# ATMEGA162.net
KiCad netlist of a schematic drawn in Altium Designer
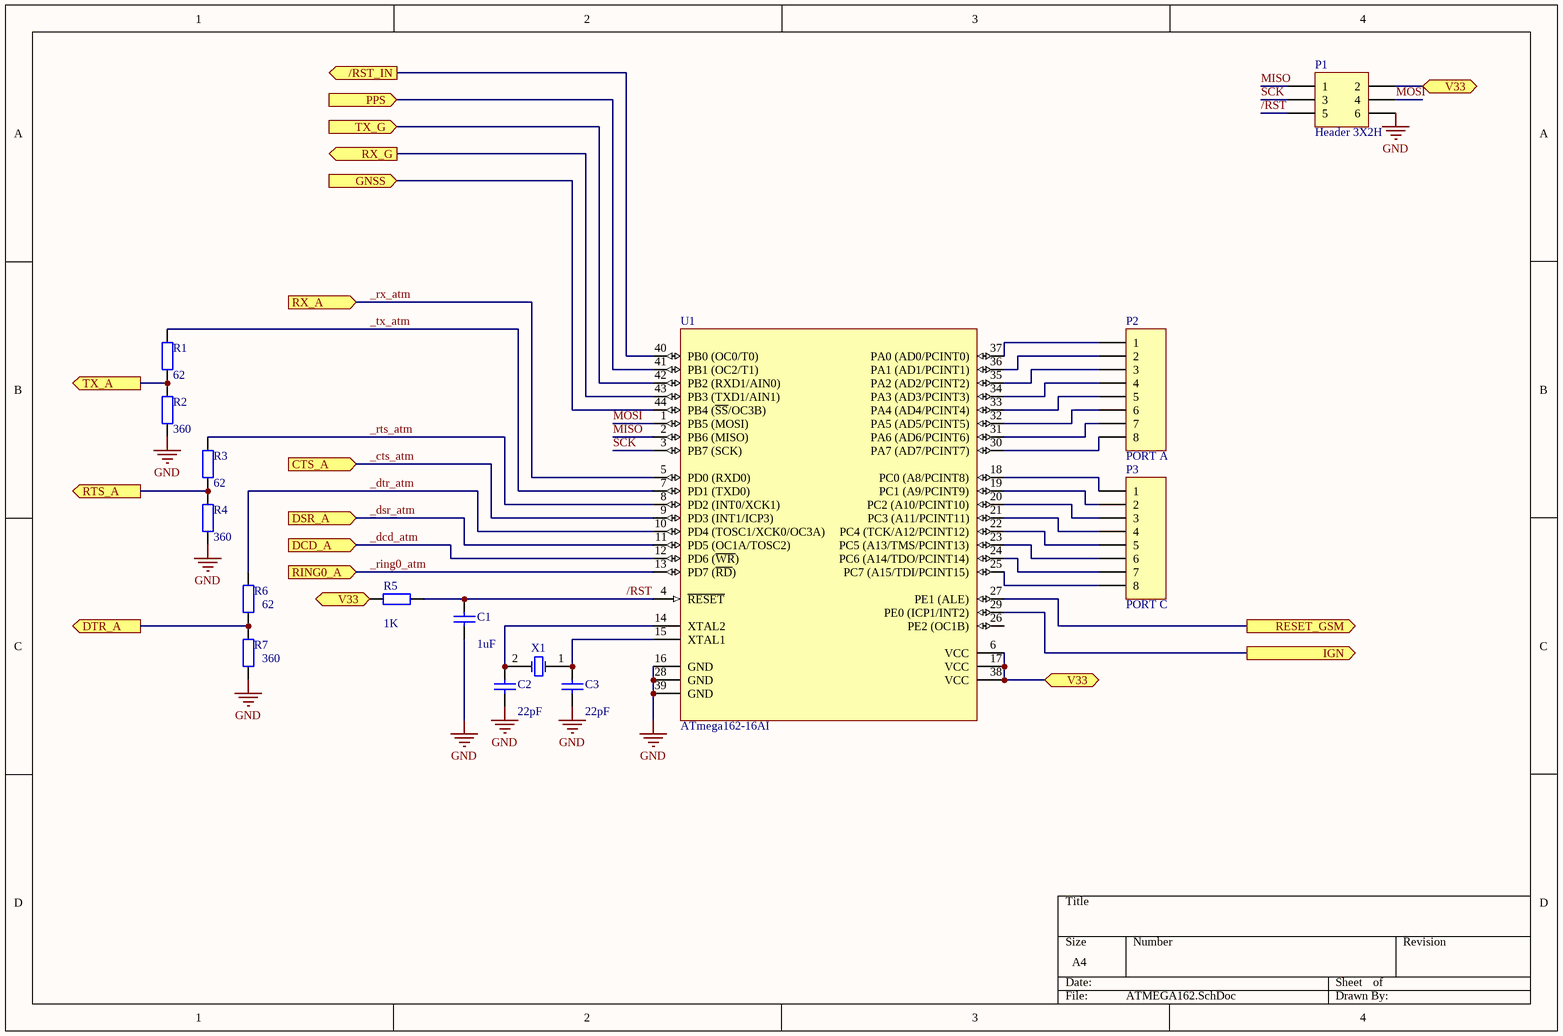
[diagram p0: ATMEGA162.SchDoc]

(export (version "E")
  (design (tool "Eeschema 10.0.6"))
  (components
    (comp (ref "C1")
      (value "1uF")
      (footprint "RAD-0.1")
      (description "Capacitor")
      (fields (field (name "Comment") "Cap") (field (name "PUBLISHER") "Altium Limited"))
      (libsource (lib "Miscellaneous Devices") (part "Cap"))
    )
    (comp (ref "C2")
      (value "22pF")
      (footprint "RAD-0.1")
      (description "Capacitor")
      (fields (field (name "Comment") "Cap") (field (name "PUBLISHER") "Altium Limited"))
      (libsource (lib "Miscellaneous Devices") (part "Cap"))
    )
    (comp (ref "C3")
      (value "22pF")
      (footprint "RAD-0.1")
      (description "Capacitor")
      (fields (field (name "Comment") "Cap") (field (name "PUBLISHER") "Altium Limited"))
      (libsource (lib "Miscellaneous Devices") (part "Cap"))
    )
    (comp (ref "P1")
      (value "Header 3X2H")
      (footprint "HDR2X3H")
      (description "Header, 3-Pin, Dual row, Right Angle")
      (fields (field (name "PUBLISHER") "Altium Limited"))
      (libsource (lib "Miscellaneous Connectors") (part "Header 3X2H"))
    )
    (comp (ref "P2")
      (value "PORT A")
      (footprint "HDR1X8H")
      (description "Header, 8-Pin, Right Angle")
      (fields (field (name "PUBLISHER") "Altium Limited"))
      (libsource (lib "Miscellaneous Connectors") (part "Header 8H"))
    )
    (comp (ref "P3")
      (value "PORT C")
      (footprint "HDR1X8H")
      (description "Header, 8-Pin, Right Angle")
      (fields (field (name "PUBLISHER") "Altium Limited"))
      (libsource (lib "Miscellaneous Connectors") (part "Header 8H"))
    )
    (comp (ref "R1")
      (value "62")
      (footprint "AXIAL-0.4")
      (description "Resistor")
      (fields (field (name "Comment") "Res2") (field (name "PUBLISHER") "Altium Limited"))
      (libsource (lib "Miscellaneous Devices") (part "Res2"))
    )
    (comp (ref "R2")
      (value "360")
      (footprint "AXIAL-0.4")
      (description "Resistor")
      (fields (field (name "Comment") "Res2") (field (name "PUBLISHER") "Altium Limited"))
      (libsource (lib "Miscellaneous Devices") (part "Res2"))
    )
    (comp (ref "R3")
      (value "62")
      (footprint "AXIAL-0.4")
      (description "Resistor")
      (fields (field (name "Comment") "Res2") (field (name "PUBLISHER") "Altium Limited"))
      (libsource (lib "Miscellaneous Devices") (part "Res2"))
    )
    (comp (ref "R4")
      (value "360")
      (footprint "AXIAL-0.4")
      (description "Resistor")
      (fields (field (name "Comment") "Res2") (field (name "PUBLISHER") "Altium Limited"))
      (libsource (lib "Miscellaneous Devices") (part "Res2"))
    )
    (comp (ref "R5")
      (value "1K")
      (footprint "AXIAL-0.4")
      (description "Resistor")
      (fields (field (name "Comment") "Res2") (field (name "PUBLISHER") "Altium Limited"))
      (libsource (lib "") (part "Res2_1"))
    )
    (comp (ref "R6")
      (value "62")
      (footprint "AXIAL-0.4")
      (description "Resistor")
      (fields (field (name "Comment") "Res2") (field (name "PUBLISHER") "Altium Limited"))
      (libsource (lib "Miscellaneous Devices") (part "Res2"))
    )
    (comp (ref "R7")
      (value "360")
      (footprint "AXIAL-0.4")
      (description "Resistor")
      (fields (field (name "Comment") "Res2") (field (name "PUBLISHER") "Altium Limited"))
      (libsource (lib "Miscellaneous Devices") (part "Res2"))
    )
    (comp (ref "U1")
      (value "ATmega162-16AI")
      (footprint "44A_L")
      (description "8-Bit AVR Microcontroller with 16K Bytes of In-System Programmable Flash Memory")
      (fields (field (name "PUBLISHER") "Altium Limited"))
      (libsource (lib "Atmel Microcontroller 8-Bit AVR") (part "ATmega162-16AI"))
    )
    (comp (ref "X1")
      (value "XTAL")
      (footprint "RAD-0.2")
      (description "Crystal Oscillator")
      (fields (field (name "PUBLISHER") "Altium Limited"))
      (libsource (lib "Miscellaneous Devices") (part "XTAL"))
    )
  )
  (nets
    (net (code "1") (name "/DTR_A") (class "Default")
      (node (ref "R6") (pin "1") (pinfunction "1_1") (pintype "passive"))
      (node (ref "R7") (pin "2") (pinfunction "2_2") (pintype "passive"))
    )
    (net (code "2") (name "/GNSS") (class "Default")
      (node (ref "U1") (pin "44") (pinfunction "PB4_(~{SS}/OC3B)_44") (pintype "bidirectional"))
    )
    (net (code "3") (name "/IGN") (class "Default")
      (node (ref "U1") (pin "29") (pinfunction "PE0_(ICP1/INT2)_29") (pintype "bidirectional"))
    )
    (net (code "4") (name "/MISO") (class "Default")
      (node (ref "P1") (pin "1") (pinfunction "1_1") (pintype "passive"))
      (node (ref "U1") (pin "2") (pinfunction "PB6_(MISO)_2") (pintype "bidirectional"))
    )
    (net (code "5") (name "/MOSI") (class "Default")
      (node (ref "P1") (pin "4") (pinfunction "4_4") (pintype "passive"))
      (node (ref "U1") (pin "1") (pinfunction "PB5_(MOSI)_1") (pintype "bidirectional"))
    )
    (net (code "6") (name "/PPS") (class "Default")
      (node (ref "U1") (pin "41") (pinfunction "PB1_(OC2/T1)_41") (pintype "bidirectional"))
    )
    (net (code "7") (name "/RESET_GSM") (class "Default")
      (node (ref "U1") (pin "27") (pinfunction "PE1_(ALE)_27") (pintype "bidirectional"))
    )
    (net (code "8") (name "/RTS_A") (class "Default")
      (node (ref "R3") (pin "1") (pinfunction "1_1") (pintype "passive"))
      (node (ref "R4") (pin "2") (pinfunction "2_2") (pintype "passive"))
    )
    (net (code "9") (name "/RX_G") (class "Default")
      (node (ref "U1") (pin "43") (pinfunction "PB3_(TXD1/AIN1)_43") (pintype "bidirectional"))
    )
    (net (code "10") (name "/SCK") (class "Default")
      (node (ref "P1") (pin "3") (pinfunction "3_3") (pintype "passive"))
      (node (ref "U1") (pin "3") (pinfunction "PB7_(SCK)_3") (pintype "bidirectional"))
    )
    (net (code "11") (name "/TX_A") (class "Default")
      (node (ref "R1") (pin "1") (pinfunction "1_1") (pintype "passive"))
      (node (ref "R2") (pin "2") (pinfunction "2_2") (pintype "passive"))
    )
    (net (code "12") (name "/TX_G") (class "Default")
      (node (ref "U1") (pin "42") (pinfunction "PB2_(RXD1/AIN0)_42") (pintype "bidirectional"))
    )
    (net (code "13") (name "/V33") (class "Default")
      (node (ref "P1") (pin "2") (pinfunction "2_2") (pintype "passive"))
      (node (ref "R5") (pin "1") (pinfunction "1_1") (pintype "passive"))
      (node (ref "U1") (pin "17") (pinfunction "VCC_17") (pintype "power_in"))
      (node (ref "U1") (pin "38") (pinfunction "VCC_38") (pintype "power_in"))
      (node (ref "U1") (pin "6") (pinfunction "VCC_6") (pintype "power_in"))
    )
    (net (code "14") (name "/_cts_atm") (class "Default")
      (node (ref "U1") (pin "9") (pinfunction "PD3_(INT1/ICP3)_9") (pintype "bidirectional"))
    )
    (net (code "15") (name "/_dcd_atm") (class "Default")
      (node (ref "U1") (pin "12") (pinfunction "PD6_(~{WR})_12") (pintype "bidirectional"))
    )
    (net (code "16") (name "/_dsr_atm") (class "Default")
      (node (ref "U1") (pin "11") (pinfunction "PD5_(OC1A/TOSC2)_11") (pintype "bidirectional"))
    )
    (net (code "17") (name "/_dtr_atm") (class "Default")
      (node (ref "R6") (pin "2") (pinfunction "2_2") (pintype "passive"))
      (node (ref "U1") (pin "10") (pinfunction "PD4_(TOSC1/XCK0/OC3A)_10") (pintype "bidirectional"))
    )
    (net (code "18") (name "/_ring0_atm") (class "Default")
      (node (ref "U1") (pin "13") (pinfunction "PD7_(~{RD})_13") (pintype "bidirectional"))
    )
    (net (code "19") (name "/_rts_atm") (class "Default")
      (node (ref "R3") (pin "2") (pinfunction "2_2") (pintype "passive"))
      (node (ref "U1") (pin "8") (pinfunction "PD2_(INT0/XCK1)_8") (pintype "bidirectional"))
    )
    (net (code "20") (name "/_rx_atm") (class "Default")
      (node (ref "U1") (pin "5") (pinfunction "PD0_(RXD0)_5") (pintype "bidirectional"))
    )
    (net (code "21") (name "/_tx_atm") (class "Default")
      (node (ref "R1") (pin "2") (pinfunction "2_2") (pintype "passive"))
      (node (ref "U1") (pin "7") (pinfunction "PD1_(TXD0)_7") (pintype "bidirectional"))
    )
    (net (code "22") (name "/{slash}RST") (class "Default")
      (node (ref "C1") (pin "2") (pinfunction "2_2") (pintype "passive"))
      (node (ref "P1") (pin "5") (pinfunction "5_5") (pintype "passive"))
      (node (ref "R5") (pin "2") (pinfunction "2_2") (pintype "passive"))
      (node (ref "U1") (pin "4") (pinfunction "~{RESET}_4") (pintype "input"))
    )
    (net (code "23") (name "/{slash}RST_IN") (class "Default")
      (node (ref "U1") (pin "40") (pinfunction "PB0_(OC0/T0)_40") (pintype "bidirectional"))
    )
    (net (code "24") (name "GND") (class "Default")
      (node (ref "C1") (pin "1") (pinfunction "1_1") (pintype "passive"))
      (node (ref "C2") (pin "1") (pinfunction "1_1") (pintype "passive"))
      (node (ref "C3") (pin "1") (pinfunction "1_1") (pintype "passive"))
      (node (ref "P1") (pin "6") (pinfunction "6_6") (pintype "passive"))
      (node (ref "R2") (pin "1") (pinfunction "1_1") (pintype "passive"))
      (node (ref "R4") (pin "1") (pinfunction "1_1") (pintype "passive"))
      (node (ref "R7") (pin "1") (pinfunction "1_1") (pintype "passive"))
      (node (ref "U1") (pin "16") (pinfunction "GND_16") (pintype "power_in"))
      (node (ref "U1") (pin "28") (pinfunction "GND_28") (pintype "power_in"))
      (node (ref "U1") (pin "39") (pinfunction "GND_39") (pintype "power_in"))
    )
    (net (code "25") (name "Net-(U1-PA0_(AD0{slash}PCINT0))") (class "Default")
      (node (ref "P2") (pin "1") (pinfunction "1_1") (pintype "passive"))
      (node (ref "U1") (pin "37") (pinfunction "PA0_(AD0/PCINT0)_37") (pintype "bidirectional"))
    )
    (net (code "26") (name "Net-(U1-PA1_(AD1{slash}PCINT1))") (class "Default")
      (node (ref "P2") (pin "2") (pinfunction "2_2") (pintype "passive"))
      (node (ref "U1") (pin "36") (pinfunction "PA1_(AD1/PCINT1)_36") (pintype "bidirectional"))
    )
    (net (code "27") (name "Net-(U1-PA2_(AD2{slash}PCINT2))") (class "Default")
      (node (ref "P2") (pin "3") (pinfunction "3_3") (pintype "passive"))
      (node (ref "U1") (pin "35") (pinfunction "PA2_(AD2/PCINT2)_35") (pintype "bidirectional"))
    )
    (net (code "28") (name "Net-(U1-PA3_(AD3{slash}PCINT3))") (class "Default")
      (node (ref "P2") (pin "4") (pinfunction "4_4") (pintype "passive"))
      (node (ref "U1") (pin "34") (pinfunction "PA3_(AD3/PCINT3)_34") (pintype "bidirectional"))
    )
    (net (code "29") (name "Net-(U1-PA4_(AD4{slash}PCINT4))") (class "Default")
      (node (ref "P2") (pin "5") (pinfunction "5_5") (pintype "passive"))
      (node (ref "U1") (pin "33") (pinfunction "PA4_(AD4/PCINT4)_33") (pintype "bidirectional"))
    )
    (net (code "30") (name "Net-(U1-PA5_(AD5{slash}PCINT5))") (class "Default")
      (node (ref "P2") (pin "6") (pinfunction "6_6") (pintype "passive"))
      (node (ref "U1") (pin "32") (pinfunction "PA5_(AD5/PCINT5)_32") (pintype "bidirectional"))
    )
    (net (code "31") (name "Net-(U1-PA6_(AD6{slash}PCINT6))") (class "Default")
      (node (ref "P2") (pin "7") (pinfunction "7_7") (pintype "passive"))
      (node (ref "U1") (pin "31") (pinfunction "PA6_(AD6/PCINT6)_31") (pintype "bidirectional"))
    )
    (net (code "32") (name "Net-(U1-PA7_(AD7{slash}PCINT7))") (class "Default")
      (node (ref "P2") (pin "8") (pinfunction "8_8") (pintype "passive"))
      (node (ref "U1") (pin "30") (pinfunction "PA7_(AD7/PCINT7)_30") (pintype "bidirectional"))
    )
    (net (code "33") (name "Net-(U1-PC0_(A8{slash}PCINT8))") (class "Default")
      (node (ref "P3") (pin "1") (pinfunction "1_1") (pintype "passive"))
      (node (ref "U1") (pin "18") (pinfunction "PC0_(A8/PCINT8)_18") (pintype "bidirectional"))
    )
    (net (code "34") (name "Net-(U1-PC1_(A9{slash}PCINT9))") (class "Default")
      (node (ref "P3") (pin "2") (pinfunction "2_2") (pintype "passive"))
      (node (ref "U1") (pin "19") (pinfunction "PC1_(A9/PCINT9)_19") (pintype "bidirectional"))
    )
    (net (code "35") (name "Net-(U1-PC2_(A10{slash}PCINT10))") (class "Default")
      (node (ref "P3") (pin "3") (pinfunction "3_3") (pintype "passive"))
      (node (ref "U1") (pin "20") (pinfunction "PC2_(A10/PCINT10)_20") (pintype "bidirectional"))
    )
    (net (code "36") (name "Net-(U1-PC3_(A11{slash}PCINT11))") (class "Default")
      (node (ref "P3") (pin "4") (pinfunction "4_4") (pintype "passive"))
      (node (ref "U1") (pin "21") (pinfunction "PC3_(A11/PCINT11)_21") (pintype "bidirectional"))
    )
    (net (code "37") (name "Net-(U1-PC4_(TCK{slash}A12{slash}PCINT12))") (class "Default")
      (node (ref "P3") (pin "5") (pinfunction "5_5") (pintype "passive"))
      (node (ref "U1") (pin "22") (pinfunction "PC4_(TCK/A12/PCINT12)_22") (pintype "bidirectional"))
    )
    (net (code "38") (name "Net-(U1-PC5_(A13{slash}TMS{slash}PCINT13))") (class "Default")
      (node (ref "P3") (pin "6") (pinfunction "6_6") (pintype "passive"))
      (node (ref "U1") (pin "23") (pinfunction "PC5_(A13/TMS/PCINT13)_23") (pintype "bidirectional"))
    )
    (net (code "39") (name "Net-(U1-PC6_(A14{slash}TDO{slash}PCINT14))") (class "Default")
      (node (ref "P3") (pin "7") (pinfunction "7_7") (pintype "passive"))
      (node (ref "U1") (pin "24") (pinfunction "PC6_(A14/TDO/PCINT14)_24") (pintype "bidirectional"))
    )
    (net (code "40") (name "Net-(U1-PC7_(A15{slash}TDI{slash}PCINT15))") (class "Default")
      (node (ref "P3") (pin "8") (pinfunction "8_8") (pintype "passive"))
      (node (ref "U1") (pin "25") (pinfunction "PC7_(A15/TDI/PCINT15)_25") (pintype "bidirectional"))
    )
    (net (code "41") (name "Net-(U1-XTAL1)") (class "Default")
      (node (ref "C3") (pin "2") (pinfunction "2_2") (pintype "passive"))
      (node (ref "U1") (pin "15") (pinfunction "XTAL1_15") (pintype "passive"))
      (node (ref "X1") (pin "1") (pinfunction "OSC1_1") (pintype "passive"))
    )
    (net (code "42") (name "Net-(U1-XTAL2)") (class "Default")
      (node (ref "C2") (pin "2") (pinfunction "2_2") (pintype "passive"))
      (node (ref "U1") (pin "14") (pinfunction "XTAL2_14") (pintype "passive"))
      (node (ref "X1") (pin "2") (pinfunction "OSC2_2") (pintype "passive"))
    )
    (net (code "43") (name "unconnected-(U1-PE2_(OC1B)-Pad26)") (class "Default")
      (node (ref "U1") (pin "26") (pinfunction "PE2_(OC1B)_26") (pintype "bidirectional"))
    )
  )
)
